# Jarduino.net
KiCad netlist of a schematic drawn in EAGLE
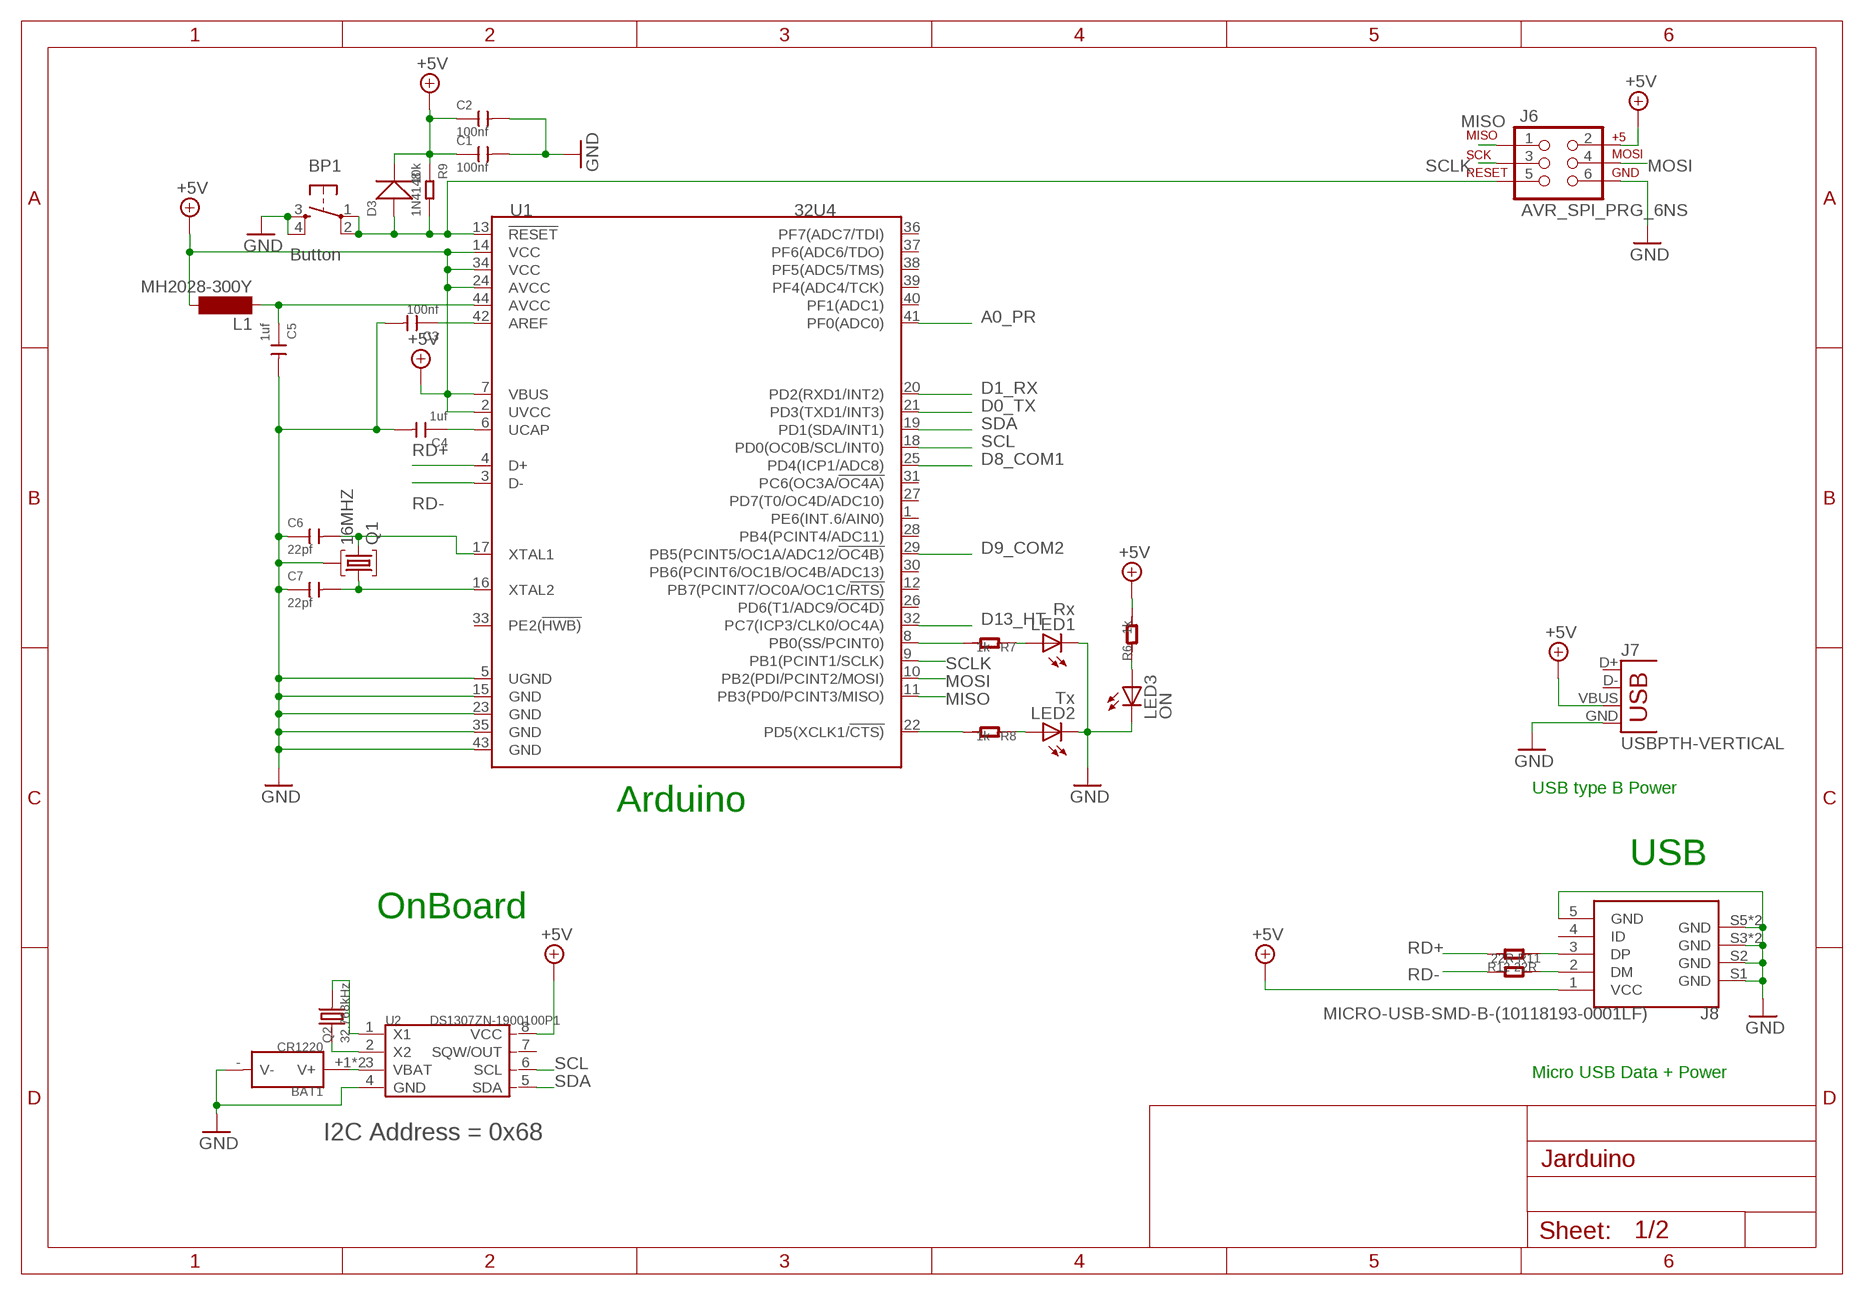
[diagram p0: schematic, sheet 1]
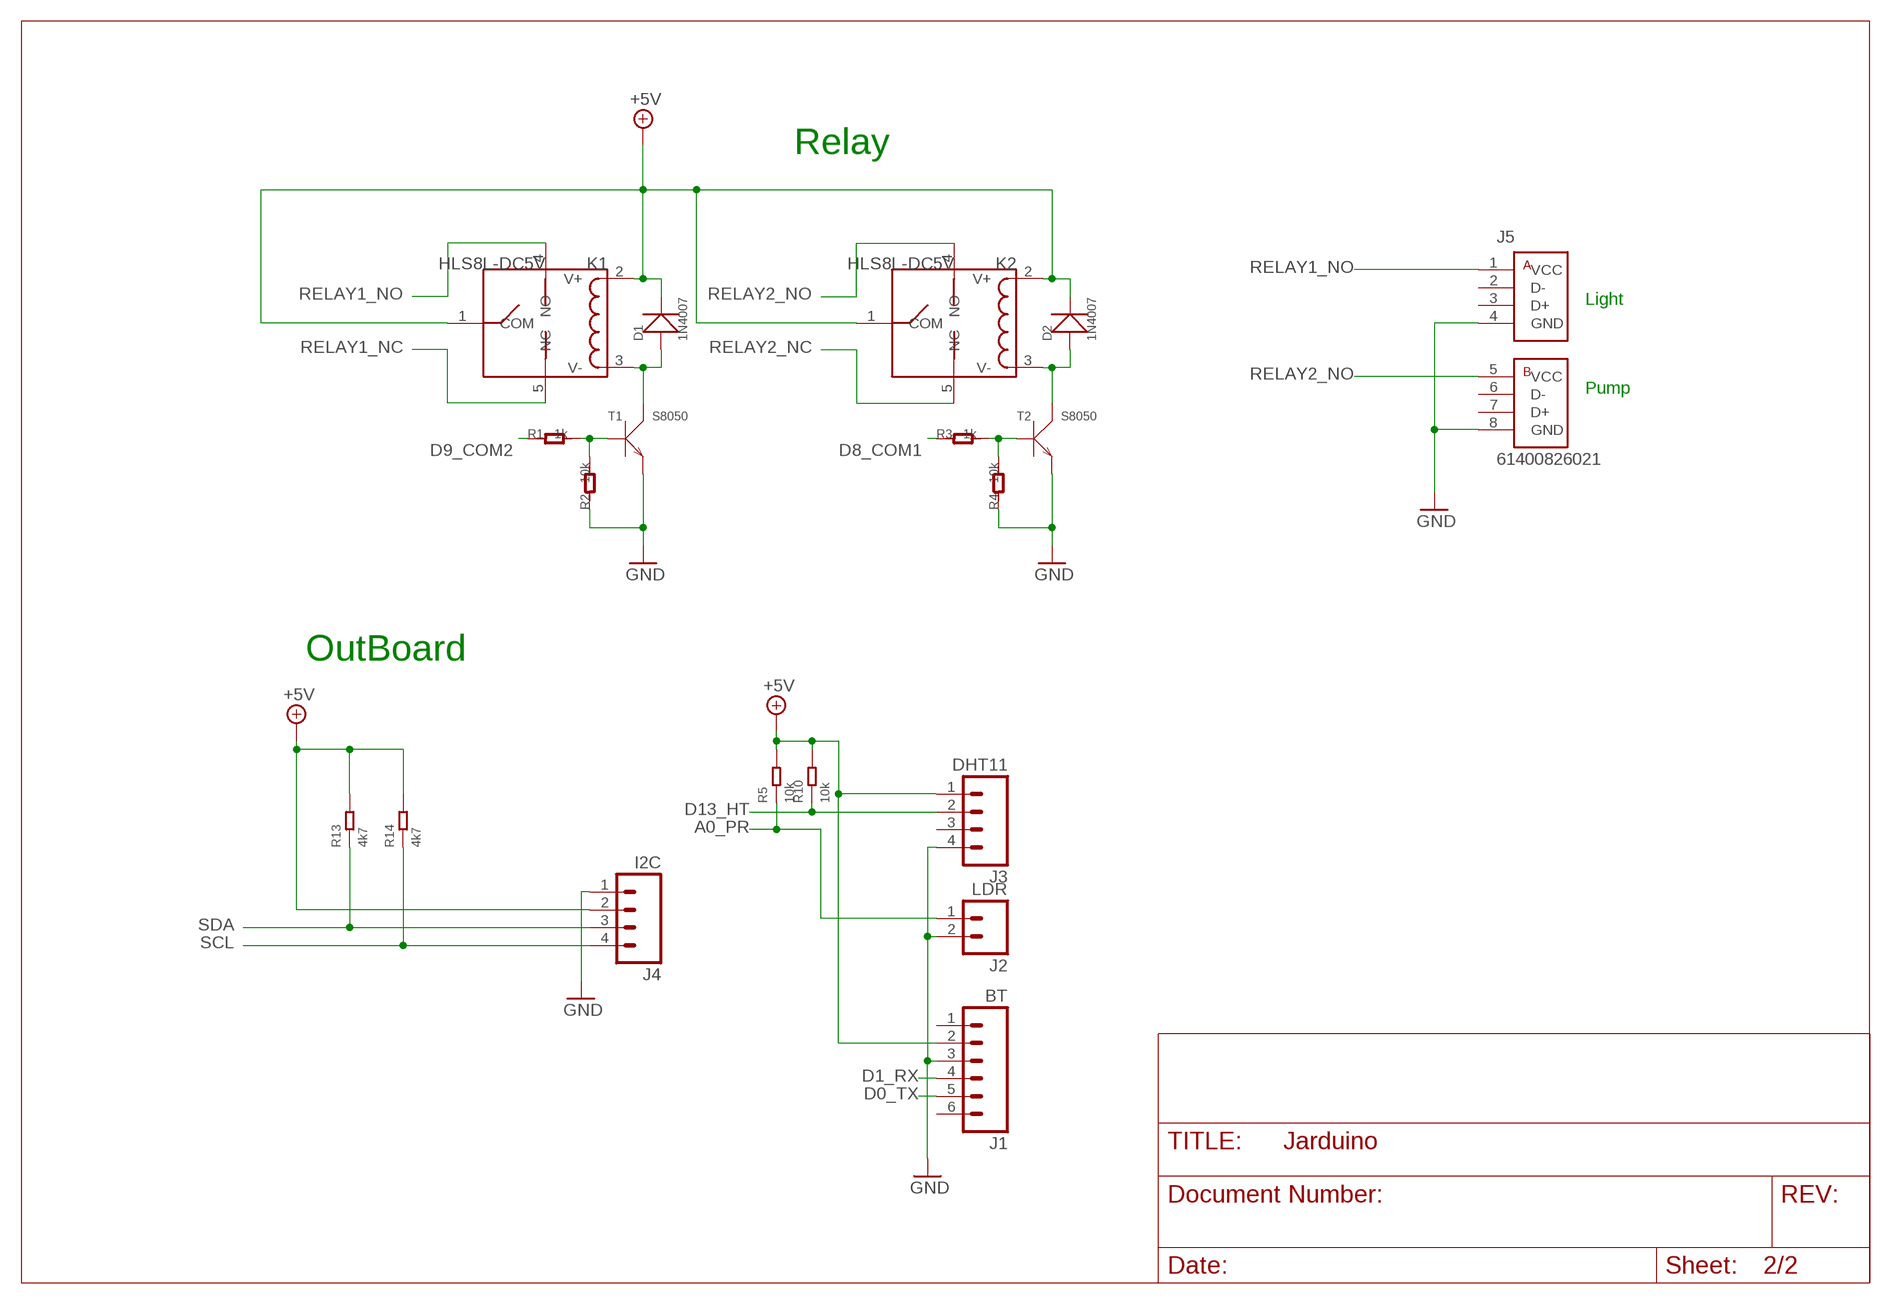
[diagram p1: schematic, sheet 2]

(export (version "E")
  (design (tool "Eeschema 10.0.6"))
  (components
    (comp (ref "D1")
      (value "1N4007")
      (footprint "eagle-import:DO-214AC")
      (libsource (lib "eagle-import") (part "DIODE-SMA"))
    )
    (comp (ref "D2")
      (value "1N4007")
      (footprint "eagle-import:DO-214AC")
      (libsource (lib "eagle-import") (part "DIODE-SMA"))
    )
    (comp (ref "J1")
      (value "BT")
      (footprint "eagle-import:MOLEX-1X6")
      (libsource (lib "eagle-import") (part "M06POLAR"))
    )
    (comp (ref "J2")
      (value "LDR")
      (footprint "eagle-import:MOLEX-1X2")
      (libsource (lib "eagle-import") (part "M02POLAR"))
    )
    (comp (ref "J3")
      (value "DHT11")
      (footprint "eagle-import:MOLEX-1X4")
      (libsource (lib "eagle-import") (part "M04POLAR"))
    )
    (comp (ref "J4")
      (value "I2C")
      (footprint "eagle-import:MOLEX-1X4")
      (libsource (lib "eagle-import") (part "M04POLAR"))
    )
    (comp (ref "J5")
      (value "61400826021")
      (footprint "eagle-import:61400826021")
      (libsource (lib "eagle-import") (part "61400826021"))
    )
    (comp (ref "K1")
      (value "HLS8L-DC5V")
      (footprint "eagle-import:5P-L19.0XW15.0XH15.0MM")
      (libsource (lib "eagle-import") (part "RELAY-HLS8L-DC5V-S-C-315030000"))
    )
    (comp (ref "K2")
      (value "HLS8L-DC5V")
      (footprint "eagle-import:5P-L19.0XW15.0XH15.0MM")
      (libsource (lib "eagle-import") (part "RELAY-HLS8L-DC5V-S-C-315030000"))
    )
    (comp (ref "R1")
      (value "1k")
      (footprint "eagle-import:R0805")
      (libsource (lib "eagle-import") (part "R-0805"))
    )
    (comp (ref "R2")
      (value "10k")
      (footprint "eagle-import:R0805")
      (libsource (lib "eagle-import") (part "R-0805"))
    )
    (comp (ref "R3")
      (value "1k")
      (footprint "eagle-import:R0805")
      (libsource (lib "eagle-import") (part "R-0805"))
    )
    (comp (ref "R4")
      (value "10k")
      (footprint "eagle-import:R0805")
      (libsource (lib "eagle-import") (part "R-0805"))
    )
    (comp (ref "R5")
      (value "10k")
      (footprint "eagle-import:R0805")
      (libsource (lib "eagle-import") (part "RES-0805"))
    )
    (comp (ref "R10")
      (value "10k")
      (footprint "eagle-import:R0805")
      (libsource (lib "eagle-import") (part "RES-0805"))
    )
    (comp (ref "R13")
      (value "4k7")
      (footprint "eagle-import:R0805")
      (libsource (lib "eagle-import") (part "RES-0805"))
    )
    (comp (ref "R14")
      (value "4k7")
      (footprint "eagle-import:R0805")
      (libsource (lib "eagle-import") (part "RES-0805"))
    )
    (comp (ref "T1")
      (value "S8050")
      (footprint "eagle-import:SOT23")
      (libsource (lib "eagle-import") (part "TRANSISTOR-NPN-''"))
    )
    (comp (ref "T2")
      (value "S8050")
      (footprint "eagle-import:SOT23")
      (libsource (lib "eagle-import") (part "TRANSISTOR-NPN-''"))
    )
    (comp (ref "BAT1")
      (value "CR1220")
      (footprint "eagle-import:METAL-CR1220-D13.5XH5.0MM")
      (libsource (lib "eagle-import") (part "BAT-HOLDER-1220"))
    )
    (comp (ref "BP1")
      (value "Button")
      (footprint "eagle-import:TACTILE-PTH")
      (libsource (lib "eagle-import") (part "TAC_SWITCHPTH"))
    )
    (comp (ref "C1")
      (value "100nf")
      (footprint "eagle-import:C0603")
      (fields (field (name "MPN") "CC0603KRX7R9BB104"))
      (libsource (lib "eagle-import") (part "CERAMIC-100NF-50V-10%-X7R(0603)"))
    )
    (comp (ref "C2")
      (value "100nf")
      (footprint "eagle-import:C0603")
      (fields (field (name "MPN") "CC0603KRX7R9BB104"))
      (libsource (lib "eagle-import") (part "CERAMIC-100NF-50V-10%-X7R(0603)"))
    )
    (comp (ref "C3")
      (value "100nf")
      (footprint "eagle-import:C0603")
      (fields (field (name "MPN") "CC0603KRX7R9BB104"))
      (libsource (lib "eagle-import") (part "CERAMIC-100NF-50V-10%-X7R(0603)"))
    )
    (comp (ref "C4")
      (value "1uf")
      (footprint "eagle-import:C0603")
      (fields (field (name "MPN") "CC0603KRX7R9BB104"))
      (libsource (lib "eagle-import") (part "CERAMIC-100NF-50V-10%-X7R(0603)"))
    )
    (comp (ref "C5")
      (value "1uf")
      (footprint "eagle-import:C0603")
      (fields (field (name "MPN") "CC0603KRX7R9BB104"))
      (libsource (lib "eagle-import") (part "CERAMIC-100NF-50V-10%-X7R(0603)"))
    )
    (comp (ref "C6")
      (value "22pf")
      (footprint "eagle-import:C0603")
      (fields (field (name "MPN") "CC0603KRX7R9BB104"))
      (libsource (lib "eagle-import") (part "CERAMIC-100NF-50V-10%-X7R(0603)"))
    )
    (comp (ref "C7")
      (value "22pf")
      (footprint "eagle-import:C0603")
      (fields (field (name "MPN") "CC0603KRX7R9BB104"))
      (libsource (lib "eagle-import") (part "CERAMIC-100NF-50V-10%-X7R(0603)"))
    )
    (comp (ref "D3")
      (value "1N4148")
      (footprint "eagle-import:LL-34")
      (libsource (lib "eagle-import") (part "DIODE'1N4148-SMD'"))
    )
    (comp (ref "J6")
      (value "AVR_SPI_PRG_6NS")
      (footprint "eagle-import:2X3-NS")
      (libsource (lib "eagle-import") (part "AVR_SPI_PRG_6NS"))
    )
    (comp (ref "J7")
      (value "USBPTH-VERTICAL")
      (footprint "eagle-import:USB-B-PTH-VERTICAL")
      (libsource (lib "eagle-import") (part "USBPTH-VERTICAL"))
    )
    (comp (ref "J8")
      (value "MICRO-USB-SMD-B-(10118193-0001LF)")
      (footprint "eagle-import:MICRO-USB5+6P-SMD-0.65-B")
      (fields (field (name "MPN") "10118193-0001LF"))
      (libsource (lib "eagle-import") (part "MICRO-USB-SMD-B-(10118193-0001LF)"))
    )
    (comp (ref "L1")
      (value "MH2028-300Y")
      (footprint "eagle-import:SM-1206")
      (libsource (lib "eagle-import") (part "SM-1206"))
    )
    (comp (ref "LED1")
      (value "Rx")
      (footprint "eagle-import:CHIP-LED0805")
      (libsource (lib "eagle-import") (part "LEDCHIP-LED0805"))
    )
    (comp (ref "LED2")
      (value "Tx")
      (footprint "eagle-import:CHIP-LED0805")
      (libsource (lib "eagle-import") (part "LEDCHIP-LED0805"))
    )
    (comp (ref "LED3")
      (value "ON")
      (footprint "eagle-import:CHIP-LED0805")
      (libsource (lib "eagle-import") (part "LEDCHIP-LED0805"))
    )
    (comp (ref "Q1")
      (value "16MHZ")
      (footprint "eagle-import:HC49U")
      (libsource (lib "eagle-import") (part "8M10AHC49T"))
    )
    (comp (ref "Q2")
      (value "32.768kHz")
      (footprint "eagle-import:2P-L3.2XW1.5MM")
      (libsource (lib "eagle-import") (part "CRYSTAL-306010055"))
    )
    (comp (ref "R6")
      (value "1k")
      (footprint "eagle-import:R0805")
      (libsource (lib "eagle-import") (part "R-0805"))
    )
    (comp (ref "R7")
      (value "1k")
      (footprint "eagle-import:R0805")
      (libsource (lib "eagle-import") (part "R-0805"))
    )
    (comp (ref "R8")
      (value "1k")
      (footprint "eagle-import:R0805")
      (libsource (lib "eagle-import") (part "R-0805"))
    )
    (comp (ref "R9")
      (value "10k")
      (footprint "eagle-import:R0805")
      (fields (field (name "MPN") "RC0805JR-071ML"))
      (libsource (lib "eagle-import") (part "SMD-RES-1M-5%-1/8W(0805)"))
    )
    (comp (ref "R11")
      (value "22R")
      (footprint "eagle-import:R0805")
      (libsource (lib "eagle-import") (part "R-0805"))
    )
    (comp (ref "R12")
      (value "22R")
      (footprint "eagle-import:R0805")
      (libsource (lib "eagle-import") (part "R-0805"))
    )
    (comp (ref "U1")
      (value "32U4")
      (footprint "eagle-import:TQFP44-0.8-9.6X9.6MM")
      (fields (field (name "MPN") "ATMEGA32U4"))
      (libsource (lib "eagle-import") (part "MCU-ATMEGA32U4(TQFP44)-AU"))
    )
    (comp (ref "U2")
      (value "DS1307ZN-1900100P1")
      (footprint "eagle-import:SOIC8")
      (libsource (lib "eagle-import") (part "DS1307ZN-1900100P1"))
    )
  )
  (nets
    (net (code "1") (name "+5V") (class "Default")
      (node (ref "C1") (pin "1") (pinfunction "1_1") (pintype "passive"))
      (node (ref "C2") (pin "1") (pinfunction "1_1") (pintype "passive"))
      (node (ref "D1") (pin "2") (pinfunction "-_2") (pintype "passive"))
      (node (ref "D2") (pin "2") (pinfunction "-_2") (pintype "passive"))
      (node (ref "D3") (pin "C") (pinfunction "-_C") (pintype "passive"))
      (node (ref "J1") (pin "2") (pinfunction "2_2") (pintype "passive"))
      (node (ref "J3") (pin "1") (pinfunction "1_1") (pintype "passive"))
      (node (ref "J4") (pin "2") (pinfunction "2_2") (pintype "passive"))
      (node (ref "J6") (pin "2") (pinfunction "2_2") (pintype "passive"))
      (node (ref "J7") (pin "VBUS") (pinfunction "VBUS_VBUS") (pintype "bidirectional"))
      (node (ref "J8") (pin "1") (pinfunction "VCC_1") (pintype "bidirectional"))
      (node (ref "K1") (pin "1") (pinfunction "COM_1") (pintype "bidirectional"))
      (node (ref "K1") (pin "2") (pinfunction "V+_2") (pintype "bidirectional"))
      (node (ref "K2") (pin "1") (pinfunction "COM_1") (pintype "bidirectional"))
      (node (ref "K2") (pin "2") (pinfunction "V+_2") (pintype "bidirectional"))
      (node (ref "L1") (pin "2") (pinfunction "2_2") (pintype "passive"))
      (node (ref "R10") (pin "2") (pinfunction "2_2") (pintype "passive"))
      (node (ref "R13") (pin "2") (pinfunction "2_2") (pintype "passive"))
      (node (ref "R14") (pin "2") (pinfunction "2_2") (pintype "passive"))
      (node (ref "R5") (pin "2") (pinfunction "2_2") (pintype "passive"))
      (node (ref "R6") (pin "2") (pinfunction "2_2") (pintype "bidirectional"))
      (node (ref "R9") (pin "1") (pinfunction "1_1") (pintype "passive"))
      (node (ref "U1") (pin "14") (pinfunction "VCC_14") (pintype "bidirectional"))
      (node (ref "U1") (pin "2") (pinfunction "UVCC_2") (pintype "bidirectional"))
      (node (ref "U1") (pin "24") (pinfunction "AVCC_24") (pintype "bidirectional"))
      (node (ref "U1") (pin "34") (pinfunction "VCC_34") (pintype "bidirectional"))
      (node (ref "U1") (pin "7") (pinfunction "VBUS_7") (pintype "bidirectional"))
      (node (ref "U2") (pin "8") (pinfunction "VCC_8") (pintype "bidirectional"))
    )
    (net (code "2") (name "A0_PR") (class "Default")
      (node (ref "J2") (pin "1") (pinfunction "1_1") (pintype "passive"))
      (node (ref "R5") (pin "1") (pinfunction "1_1") (pintype "passive"))
      (node (ref "U1") (pin "41") (pinfunction "PF0(ADC0)_41") (pintype "bidirectional"))
    )
    (net (code "3") (name "D0_TX") (class "Default")
      (node (ref "J1") (pin "5") (pinfunction "5_5") (pintype "passive"))
      (node (ref "U1") (pin "21") (pinfunction "PD3(TXD1/INT3)_21") (pintype "bidirectional"))
    )
    (net (code "4") (name "D1_RX") (class "Default")
      (node (ref "J1") (pin "4") (pinfunction "4_4") (pintype "passive"))
      (node (ref "U1") (pin "20") (pinfunction "PD2(RXD1/INT2)_20") (pintype "bidirectional"))
    )
    (net (code "5") (name "D8_COM1") (class "Default")
      (node (ref "R3") (pin "1") (pinfunction "1_1") (pintype "bidirectional"))
      (node (ref "U1") (pin "25") (pinfunction "PD4(ICP1/ADC8)_25") (pintype "bidirectional"))
    )
    (net (code "6") (name "D9_COM2") (class "Default")
      (node (ref "R1") (pin "1") (pinfunction "1_1") (pintype "bidirectional"))
      (node (ref "U1") (pin "29") (pinfunction "PB5(PCINT5/OC1A/ADC12/~{OC4B})_29") (pintype "bidirectional"))
    )
    (net (code "7") (name "D13_HT") (class "Default")
      (node (ref "J3") (pin "2") (pinfunction "2_2") (pintype "passive"))
      (node (ref "R10") (pin "1") (pinfunction "1_1") (pintype "passive"))
      (node (ref "U1") (pin "32") (pinfunction "PC7(ICP3/CLK0/OC4A)_32") (pintype "bidirectional"))
    )
    (net (code "8") (name "GND") (class "Default")
      (node (ref "BAT1") (pin "-") (pinfunction "V-_-") (pintype "bidirectional"))
      (node (ref "BP1") (pin "3") (pinfunction "3_3") (pintype "passive"))
      (node (ref "BP1") (pin "4") (pinfunction "4_4") (pintype "passive"))
      (node (ref "C1") (pin "2") (pinfunction "2_2") (pintype "passive"))
      (node (ref "C2") (pin "2") (pinfunction "2_2") (pintype "passive"))
      (node (ref "C3") (pin "2") (pinfunction "2_2") (pintype "passive"))
      (node (ref "C4") (pin "2") (pinfunction "2_2") (pintype "passive"))
      (node (ref "C5") (pin "2") (pinfunction "2_2") (pintype "passive"))
      (node (ref "C6") (pin "1") (pinfunction "1_1") (pintype "passive"))
      (node (ref "C7") (pin "1") (pinfunction "1_1") (pintype "passive"))
      (node (ref "J1") (pin "3") (pinfunction "3_3") (pintype "passive"))
      (node (ref "J2") (pin "2") (pinfunction "2_2") (pintype "passive"))
      (node (ref "J3") (pin "4") (pinfunction "4_4") (pintype "passive"))
      (node (ref "J4") (pin "1") (pinfunction "1_1") (pintype "passive"))
      (node (ref "J5") (pin "4") (pinfunction "GND_4") (pintype "bidirectional"))
      (node (ref "J5") (pin "8") (pinfunction "GND_8") (pintype "bidirectional"))
      (node (ref "J6") (pin "6") (pinfunction "6_6") (pintype "passive"))
      (node (ref "J7") (pin "GND") (pinfunction "GND_GND") (pintype "bidirectional"))
      (node (ref "J8") (pin "5") (pinfunction "GND_5") (pintype "bidirectional"))
      (node (ref "J8") (pin "S1") (pinfunction "GND_S1") (pintype "bidirectional"))
      (node (ref "J8") (pin "S2") (pinfunction "GND_S2") (pintype "bidirectional"))
      (node (ref "J8") (pin "S3") (pinfunction "GND_S3") (pintype "bidirectional"))
      (node (ref "J8") (pin "S4") (pinfunction "GND_S4") (pintype "bidirectional"))
      (node (ref "J8") (pin "S5") (pinfunction "GND_S5") (pintype "bidirectional"))
      (node (ref "J8") (pin "S6") (pinfunction "GND_S6") (pintype "bidirectional"))
      (node (ref "LED1") (pin "C") (pinfunction "C_C") (pintype "passive"))
      (node (ref "LED2") (pin "C") (pinfunction "C_C") (pintype "passive"))
      (node (ref "LED3") (pin "C") (pinfunction "C_C") (pintype "passive"))
      (node (ref "Q1") (pin "2") (pinfunction "2_2") (pintype "passive"))
      (node (ref "R2") (pin "1") (pinfunction "1_1") (pintype "bidirectional"))
      (node (ref "R4") (pin "1") (pinfunction "1_1") (pintype "bidirectional"))
      (node (ref "T1") (pin "2") (pinfunction "E_2") (pintype "passive"))
      (node (ref "T2") (pin "2") (pinfunction "E_2") (pintype "passive"))
      (node (ref "U1") (pin "15") (pinfunction "GND_15") (pintype "bidirectional"))
      (node (ref "U1") (pin "23") (pinfunction "GND_23") (pintype "bidirectional"))
      (node (ref "U1") (pin "35") (pinfunction "GND_35") (pintype "bidirectional"))
      (node (ref "U1") (pin "43") (pinfunction "GND_43") (pintype "bidirectional"))
      (node (ref "U1") (pin "5") (pinfunction "UGND_5") (pintype "bidirectional"))
      (node (ref "U2") (pin "4") (pinfunction "GND_4") (pintype "bidirectional"))
    )
    (net (code "9") (name "MISO") (class "Default")
      (node (ref "J6") (pin "1") (pinfunction "1_1") (pintype "passive"))
      (node (ref "U1") (pin "11") (pinfunction "PB3(PD0/PCINT3/MISO)_11") (pintype "bidirectional"))
    )
    (net (code "10") (name "MOSI") (class "Default")
      (node (ref "J6") (pin "4") (pinfunction "4_4") (pintype "passive"))
      (node (ref "U1") (pin "10") (pinfunction "PB2(PDI/PCINT2/MOSI)_10") (pintype "bidirectional"))
    )
    (net (code "11") (name "Net-(C5-Pad1)") (class "Default")
      (node (ref "C5") (pin "1") (pinfunction "1_1") (pintype "passive"))
      (node (ref "L1") (pin "1") (pinfunction "1_1") (pintype "passive"))
      (node (ref "U1") (pin "44") (pinfunction "AVCC_44") (pintype "bidirectional"))
    )
    (net (code "12") (name "Net-(D1-+)") (class "Default")
      (node (ref "D1") (pin "1") (pinfunction "+_1") (pintype "passive"))
      (node (ref "K1") (pin "3") (pinfunction "V-_3") (pintype "bidirectional"))
      (node (ref "T1") (pin "3") (pinfunction "C_3") (pintype "passive"))
    )
    (net (code "13") (name "Net-(D2-+)") (class "Default")
      (node (ref "D2") (pin "1") (pinfunction "+_1") (pintype "passive"))
      (node (ref "K2") (pin "3") (pinfunction "V-_3") (pintype "bidirectional"))
      (node (ref "T2") (pin "3") (pinfunction "C_3") (pintype "passive"))
    )
    (net (code "14") (name "Net-(D3-+)") (class "Default")
      (node (ref "BP1") (pin "1") (pinfunction "1_1") (pintype "passive"))
      (node (ref "BP1") (pin "2") (pinfunction "2_2") (pintype "passive"))
      (node (ref "D3") (pin "A") (pinfunction "+_A") (pintype "passive"))
      (node (ref "J6") (pin "5") (pinfunction "5_5") (pintype "passive"))
      (node (ref "R9") (pin "2") (pinfunction "2_2") (pintype "passive"))
      (node (ref "U1") (pin "13") (pinfunction "~{RESET}_13") (pintype "bidirectional"))
    )
    (net (code "15") (name "Net-(J8-DM)") (class "Default")
      (node (ref "J8") (pin "2") (pinfunction "DM_2") (pintype "bidirectional"))
      (node (ref "R12") (pin "2") (pinfunction "2_2") (pintype "bidirectional"))
    )
    (net (code "16") (name "Net-(J8-DP)") (class "Default")
      (node (ref "J8") (pin "3") (pinfunction "DP_3") (pintype "bidirectional"))
      (node (ref "R11") (pin "1") (pinfunction "1_1") (pintype "bidirectional"))
    )
    (net (code "17") (name "Net-(LED1-PadA)") (class "Default")
      (node (ref "LED1") (pin "A") (pinfunction "A_A") (pintype "passive"))
      (node (ref "R7") (pin "1") (pinfunction "1_1") (pintype "bidirectional"))
    )
    (net (code "18") (name "Net-(LED2-PadA)") (class "Default")
      (node (ref "LED2") (pin "A") (pinfunction "A_A") (pintype "passive"))
      (node (ref "R8") (pin "1") (pinfunction "1_1") (pintype "bidirectional"))
    )
    (net (code "19") (name "Net-(LED3-PadA)") (class "Default")
      (node (ref "LED3") (pin "A") (pinfunction "A_A") (pintype "passive"))
      (node (ref "R6") (pin "1") (pinfunction "1_1") (pintype "bidirectional"))
    )
    (net (code "20") (name "Net-(T1-B)") (class "Default")
      (node (ref "R1") (pin "2") (pinfunction "2_2") (pintype "bidirectional"))
      (node (ref "R2") (pin "2") (pinfunction "2_2") (pintype "bidirectional"))
      (node (ref "T1") (pin "1") (pinfunction "B_1") (pintype "passive"))
    )
    (net (code "21") (name "Net-(T2-B)") (class "Default")
      (node (ref "R3") (pin "2") (pinfunction "2_2") (pintype "bidirectional"))
      (node (ref "R4") (pin "2") (pinfunction "2_2") (pintype "bidirectional"))
      (node (ref "T2") (pin "1") (pinfunction "B_1") (pintype "passive"))
    )
    (net (code "22") (name "Net-(U1-AREF)") (class "Default")
      (node (ref "C3") (pin "1") (pinfunction "1_1") (pintype "passive"))
      (node (ref "U1") (pin "42") (pinfunction "AREF_42") (pintype "bidirectional"))
    )
    (net (code "23") (name "Net-(U1-PB0(SS{slash}PCINT0))") (class "Default")
      (node (ref "R7") (pin "2") (pinfunction "2_2") (pintype "bidirectional"))
      (node (ref "U1") (pin "8") (pinfunction "PB0(SS/PCINT0)_8") (pintype "bidirectional"))
    )
    (net (code "24") (name "Net-(U1-PD5(XCLK1{slash}~{CTS}))") (class "Default")
      (node (ref "R8") (pin "2") (pinfunction "2_2") (pintype "bidirectional"))
      (node (ref "U1") (pin "22") (pinfunction "PD5(XCLK1/~{CTS})_22") (pintype "bidirectional"))
    )
    (net (code "25") (name "Net-(U1-UCAP)") (class "Default")
      (node (ref "C4") (pin "1") (pinfunction "1_1") (pintype "passive"))
      (node (ref "U1") (pin "6") (pinfunction "UCAP_6") (pintype "bidirectional"))
    )
    (net (code "26") (name "Net-(U1-XTAL1)") (class "Default")
      (node (ref "C6") (pin "2") (pinfunction "2_2") (pintype "passive"))
      (node (ref "Q1") (pin "3") (pinfunction "3_3") (pintype "passive"))
      (node (ref "U1") (pin "17") (pinfunction "XTAL1_17") (pintype "bidirectional"))
    )
    (net (code "27") (name "Net-(U1-XTAL2)") (class "Default")
      (node (ref "C7") (pin "2") (pinfunction "2_2") (pintype "passive"))
      (node (ref "Q1") (pin "1") (pinfunction "1_1") (pintype "passive"))
      (node (ref "U1") (pin "16") (pinfunction "XTAL2_16") (pintype "bidirectional"))
    )
    (net (code "28") (name "Net-(U2-VBAT)") (class "Default")
      (node (ref "BAT1") (pin "+1") (pinfunction "V+_+1") (pintype "bidirectional"))
      (node (ref "BAT1") (pin "+2") (pinfunction "V+_+2") (pintype "bidirectional"))
      (node (ref "U2") (pin "3") (pinfunction "VBAT_3") (pintype "bidirectional"))
    )
    (net (code "29") (name "Net-(U2-X1)") (class "Default")
      (node (ref "Q2") (pin "2") (pinfunction "2_2") (pintype "passive"))
      (node (ref "U2") (pin "1") (pinfunction "X1_1") (pintype "bidirectional"))
    )
    (net (code "30") (name "Net-(U2-X2)") (class "Default")
      (node (ref "Q2") (pin "1") (pinfunction "1_1") (pintype "passive"))
      (node (ref "U2") (pin "2") (pinfunction "X2_2") (pintype "bidirectional"))
    )
    (net (code "31") (name "RD+") (class "Default")
      (node (ref "R11") (pin "2") (pinfunction "2_2") (pintype "bidirectional"))
      (node (ref "U1") (pin "4") (pinfunction "D+_4") (pintype "bidirectional"))
    )
    (net (code "32") (name "RD-") (class "Default")
      (node (ref "R12") (pin "1") (pinfunction "1_1") (pintype "bidirectional"))
      (node (ref "U1") (pin "3") (pinfunction "D-_3") (pintype "bidirectional"))
    )
    (net (code "33") (name "RELAY1_NC") (class "Default")
      (node (ref "K1") (pin "5") (pinfunction "NC_5") (pintype "bidirectional"))
    )
    (net (code "34") (name "RELAY1_NO") (class "Default")
      (node (ref "J5") (pin "1") (pinfunction "VCC_1") (pintype "bidirectional"))
      (node (ref "K1") (pin "4") (pinfunction "NO_4") (pintype "bidirectional"))
    )
    (net (code "35") (name "RELAY2_NC") (class "Default")
      (node (ref "K2") (pin "5") (pinfunction "NC_5") (pintype "bidirectional"))
    )
    (net (code "36") (name "RELAY2_NO") (class "Default")
      (node (ref "J5") (pin "5") (pinfunction "VCC_5") (pintype "bidirectional"))
      (node (ref "K2") (pin "4") (pinfunction "NO_4") (pintype "bidirectional"))
    )
    (net (code "37") (name "SCL") (class "Default")
      (node (ref "J4") (pin "4") (pinfunction "4_4") (pintype "passive"))
      (node (ref "R14") (pin "1") (pinfunction "1_1") (pintype "passive"))
      (node (ref "U1") (pin "18") (pinfunction "PD0(OC0B/SCL/INT0)_18") (pintype "bidirectional"))
      (node (ref "U2") (pin "6") (pinfunction "SCL_6") (pintype "bidirectional"))
    )
    (net (code "38") (name "SCLK") (class "Default")
      (node (ref "J6") (pin "3") (pinfunction "3_3") (pintype "passive"))
      (node (ref "U1") (pin "9") (pinfunction "PB1(PCINT1/SCLK)_9") (pintype "bidirectional"))
    )
    (net (code "39") (name "SDA") (class "Default")
      (node (ref "J4") (pin "3") (pinfunction "3_3") (pintype "passive"))
      (node (ref "R13") (pin "1") (pinfunction "1_1") (pintype "passive"))
      (node (ref "U1") (pin "19") (pinfunction "PD1(SDA/INT1)_19") (pintype "bidirectional"))
      (node (ref "U2") (pin "5") (pinfunction "SDA_5") (pintype "bidirectional"))
    )
    (net (code "40") (name "unconnected-(J1-Pad1)") (class "Default")
      (node (ref "J1") (pin "1") (pinfunction "1_1") (pintype "passive"))
    )
    (net (code "41") (name "unconnected-(J1-Pad6)") (class "Default")
      (node (ref "J1") (pin "6") (pinfunction "6_6") (pintype "passive"))
    )
    (net (code "42") (name "unconnected-(J3-Pad3)") (class "Default")
      (node (ref "J3") (pin "3") (pinfunction "3_3") (pintype "passive"))
    )
    (net (code "43") (name "unconnected-(J5-D+-Pad3)") (class "Default")
      (node (ref "J5") (pin "3") (pinfunction "D+_3") (pintype "bidirectional"))
    )
    (net (code "44") (name "unconnected-(J5-D+-Pad7)") (class "Default")
      (node (ref "J5") (pin "7") (pinfunction "D+_7") (pintype "bidirectional"))
    )
    (net (code "45") (name "unconnected-(J5-D--Pad2)") (class "Default")
      (node (ref "J5") (pin "2") (pinfunction "D-_2") (pintype "bidirectional"))
    )
    (net (code "46") (name "unconnected-(J5-D--Pad6)") (class "Default")
      (node (ref "J5") (pin "6") (pinfunction "D-_6") (pintype "bidirectional"))
    )
    (net (code "47") (name "unconnected-(J7-PadD+)") (class "Default")
      (node (ref "J7") (pin "D+") (pinfunction "D+_D+") (pintype "bidirectional"))
    )
    (net (code "48") (name "unconnected-(J7-PadD-)") (class "Default")
      (node (ref "J7") (pin "D-") (pinfunction "D-_D-") (pintype "bidirectional"))
    )
    (net (code "49") (name "unconnected-(J8-ID-Pad4)") (class "Default")
      (node (ref "J8") (pin "4") (pinfunction "ID_4") (pintype "bidirectional"))
    )
    (net (code "50") (name "unconnected-(U1-PB4(PCINT4{slash}ADC11)-Pad28)") (class "Default")
      (node (ref "U1") (pin "28") (pinfunction "PB4(PCINT4/ADC11)_28") (pintype "bidirectional"))
    )
    (net (code "51") (name "unconnected-(U1-PB6(PCINT6{slash}OC1B{slash}OC4B{slash}ADC13)-Pad30)") (class "Default")
      (node (ref "U1") (pin "30") (pinfunction "PB6(PCINT6/OC1B/OC4B/ADC13)_30") (pintype "bidirectional"))
    )
    (net (code "52") (name "unconnected-(U1-PB7(PCINT7{slash}OC0A{slash}OC1C{slash}~{RTS})-Pad12)") (class "Default")
      (node (ref "U1") (pin "12") (pinfunction "PB7(PCINT7/OC0A/OC1C/~{RTS})_12") (pintype "bidirectional"))
    )
    (net (code "53") (name "unconnected-(U1-PC6(OC3A{slash}~{OC4A})-Pad31)") (class "Default")
      (node (ref "U1") (pin "31") (pinfunction "PC6(OC3A/~{OC4A})_31") (pintype "bidirectional"))
    )
    (net (code "54") (name "unconnected-(U1-PD6(T1{slash}ADC9{slash}~{OC4D})-Pad26)") (class "Default")
      (node (ref "U1") (pin "26") (pinfunction "PD6(T1/ADC9/~{OC4D})_26") (pintype "bidirectional"))
    )
    (net (code "55") (name "unconnected-(U1-PD7(T0{slash}OC4D{slash}ADC10)-Pad27)") (class "Default")
      (node (ref "U1") (pin "27") (pinfunction "PD7(T0/OC4D/ADC10)_27") (pintype "bidirectional"))
    )
    (net (code "56") (name "unconnected-(U1-PE2(~{HWB})-Pad33)") (class "Default")
      (node (ref "U1") (pin "33") (pinfunction "PE2(~{HWB})_33") (pintype "bidirectional"))
    )
    (net (code "57") (name "unconnected-(U1-PE6(INT.6{slash}AIN0)-Pad1)") (class "Default")
      (node (ref "U1") (pin "1") (pinfunction "PE6(INT.6/AIN0)_1") (pintype "bidirectional"))
    )
    (net (code "58") (name "unconnected-(U1-PF1(ADC1)-Pad40)") (class "Default")
      (node (ref "U1") (pin "40") (pinfunction "PF1(ADC1)_40") (pintype "bidirectional"))
    )
    (net (code "59") (name "unconnected-(U1-PF4(ADC4{slash}TCK)-Pad39)") (class "Default")
      (node (ref "U1") (pin "39") (pinfunction "PF4(ADC4/TCK)_39") (pintype "bidirectional"))
    )
    (net (code "60") (name "unconnected-(U1-PF5(ADC5{slash}TMS)-Pad38)") (class "Default")
      (node (ref "U1") (pin "38") (pinfunction "PF5(ADC5/TMS)_38") (pintype "bidirectional"))
    )
    (net (code "61") (name "unconnected-(U1-PF6(ADC6{slash}TDO)-Pad37)") (class "Default")
      (node (ref "U1") (pin "37") (pinfunction "PF6(ADC6/TDO)_37") (pintype "bidirectional"))
    )
    (net (code "62") (name "unconnected-(U1-PF7(ADC7{slash}TDI)-Pad36)") (class "Default")
      (node (ref "U1") (pin "36") (pinfunction "PF7(ADC7/TDI)_36") (pintype "bidirectional"))
    )
    (net (code "63") (name "unconnected-(U2-SQW{slash}OUT-Pad7)") (class "Default")
      (node (ref "U2") (pin "7") (pinfunction "SQW/OUT_7") (pintype "bidirectional"))
    )
  )
)
